# 5__Analog_input_filters.net
KiCad netlist of a schematic drawn in Altium Designer
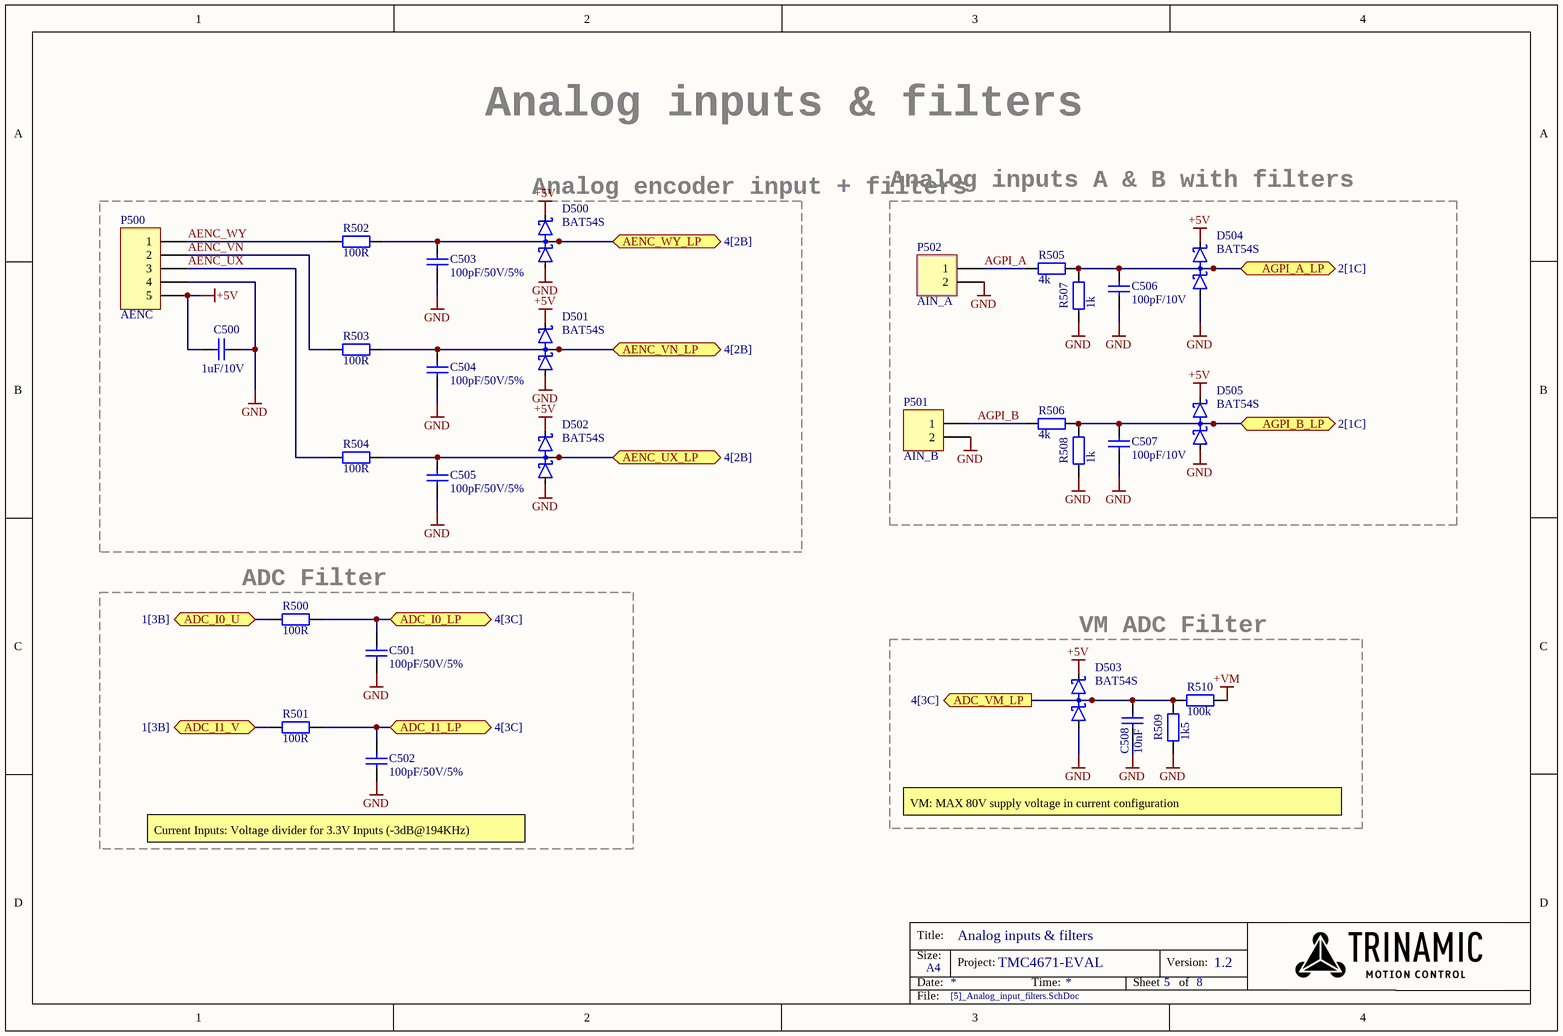
[diagram p0: [5]_Analog_input_filters.SchDoc]

(export (version "E")
  (design (tool "Eeschema 10.0.6"))
  (components
    (comp (ref "C500")
      (value "1uF/10V")
      (footprint "C0603")
      (description "SMD Multilayer Ceramic Capacitor, 0603 [1608 Metric], 1 µF, 10 V, ± 10%, X5R, MC Series")
      (fields (field (name "MF") "MULTICOMP") (field (name "MPN") "MC0603X105K100CT"))
      (libsource (lib "SMD_Passives") (part "C, 1 µF, 10 V, ± 10%, X5R, MC Series, 0603 [1608 Metric]"))
    )
    (comp (ref "C501")
      (value "100pF/50V/5%")
      (footprint "C0603")
      (description "SMD Multilayer Ceramic Capacitor, 0603 [1608 Metric], 100 pF, 50 V, ± 5%, C0G / NP0, MC Series")
      (fields (field (name "MF") "MULTICOMP") (field (name "MPN") "MC0603N101J500CT"))
      (libsource (lib "SMD_Passives") (part "C, 100 pF, 50 V, ± 5%, C0G / NP0, MC Series, 0603 [1608 Metric]"))
    )
    (comp (ref "C502")
      (value "100pF/50V/5%")
      (footprint "C0603")
      (description "SMD Multilayer Ceramic Capacitor, 0603 [1608 Metric], 100 pF, 50 V, ± 5%, C0G / NP0, MC Series")
      (fields (field (name "MF") "MULTICOMP") (field (name "MPN") "MC0603N101J500CT"))
      (libsource (lib "SMD_Passives") (part "C, 100 pF, 50 V, ± 5%, C0G / NP0, MC Series, 0603 [1608 Metric]"))
    )
    (comp (ref "C503")
      (value "100pF/50V/5%")
      (footprint "C0603")
      (description "SMD Multilayer Ceramic Capacitor, 0603 [1608 Metric], 100 pF, 50 V, ± 5%, C0G / NP0, MC Series")
      (fields (field (name "MF") "MULTICOMP") (field (name "MPN") "MC0603N101J500CT"))
      (libsource (lib "SMD_Passives") (part "C, 100 pF, 50 V, ± 5%, C0G / NP0, MC Series, 0603 [1608 Metric]"))
    )
    (comp (ref "C504")
      (value "100pF/50V/5%")
      (footprint "C0603")
      (description "SMD Multilayer Ceramic Capacitor, 0603 [1608 Metric], 100 pF, 50 V, ± 5%, C0G / NP0, MC Series")
      (fields (field (name "MF") "MULTICOMP") (field (name "MPN") "MC0603N101J500CT"))
      (libsource (lib "SMD_Passives") (part "C, 100 pF, 50 V, ± 5%, C0G / NP0, MC Series, 0603 [1608 Metric]"))
    )
    (comp (ref "C505")
      (value "100pF/50V/5%")
      (footprint "C0603")
      (description "SMD Multilayer Ceramic Capacitor, 0603 [1608 Metric], 100 pF, 50 V, ± 5%, C0G / NP0, MC Series")
      (fields (field (name "MF") "MULTICOMP") (field (name "MPN") "MC0603N101J500CT"))
      (libsource (lib "SMD_Passives") (part "C, 100 pF, 50 V, ± 5%, C0G / NP0, MC Series, 0603 [1608 Metric]"))
    )
    (comp (ref "C506")
      (value "100pF/10V")
      (footprint "C0603")
      (description "SMD Multilayer Ceramic Capacitor, 0603 [1608 Metric], 100 pF, 10 V, ± 1%, C0G / NP0, MCMT Series")
      (fields (field (name "MF") "MULTICOMP") (field (name "MPN") "MCMT18N101F100CT"))
      (libsource (lib "SMD_Passives") (part "C, 100 pF, 10 V, ± 1%, C0G / NP0, MCMT Series, 0603 [1608 Metric]"))
    )
    (comp (ref "C507")
      (value "100pF/10V")
      (footprint "C0603")
      (description "SMD Multilayer Ceramic Capacitor, 0603 [1608 Metric], 100 pF, 10 V, ± 1%, C0G / NP0, MCMT Series")
      (fields (field (name "MF") "MULTICOMP") (field (name "MPN") "MCMT18N101F100CT"))
      (libsource (lib "SMD_Passives") (part "C, 100 pF, 10 V, ± 1%, C0G / NP0, MCMT Series, 0603 [1608 Metric]"))
    )
    (comp (ref "C508")
      (value "10nF")
      (footprint "C0603")
      (description "SMD Multilayer Ceramic Capacitor, 0603 [1608 Metric], 0.01 µF, 10 V, ± 10%, X7R, MCSH Series")
      (fields (field (name "MF") "MULTICOMP") (field (name "MPN") "MCSH18B103K100CT"))
      (libsource (lib "SMD_Passives") (part "C, 10nF, 10 V, ± 10%, X7R, 0603"))
    )
    (comp (ref "D500")
      (value "BAT54S")
      (footprint "SOT95P237X130-3N")
      (description "Small Signal Schottky Diode, Dual Series, 30 V, 200 mA, 1 V, 600 mA, 125 °C")
      (fields (field (name "MF") "TAIWAN SEMICONDUCTOR"))
      (libsource (lib "TMC4671-EVAL_V1_0") (part "BAT54S"))
    )
    (comp (ref "D501")
      (value "BAT54S")
      (footprint "SOT95P237X130-3N")
      (description "Small Signal Schottky Diode, Dual Series, 30 V, 200 mA, 1 V, 600 mA, 125 °C")
      (fields (field (name "MF") "TAIWAN SEMICONDUCTOR"))
      (libsource (lib "TMC4671-EVAL_V1_0") (part "BAT54S"))
    )
    (comp (ref "D502")
      (value "BAT54S")
      (footprint "SOT95P237X130-3N")
      (description "Small Signal Schottky Diode, Dual Series, 30 V, 200 mA, 1 V, 600 mA, 125 °C")
      (fields (field (name "MF") "TAIWAN SEMICONDUCTOR"))
      (libsource (lib "TMC4671-EVAL_V1_0") (part "BAT54S"))
    )
    (comp (ref "D503")
      (value "BAT54S")
      (footprint "SOT95P237X130-3N")
      (description "Small Signal Schottky Diode, Dual Series, 30 V, 200 mA, 1 V, 600 mA, 125 °C")
      (fields (field (name "MF") "TAIWAN SEMICONDUCTOR"))
      (libsource (lib "TMC4671-EVAL_V1_0") (part "BAT54S"))
    )
    (comp (ref "D504")
      (value "BAT54S")
      (footprint "SOT95P237X130-3N")
      (description "Small Signal Schottky Diode, Dual Series, 30 V, 200 mA, 1 V, 600 mA, 125 °C")
      (fields (field (name "MF") "TAIWAN SEMICONDUCTOR"))
      (libsource (lib "TMC4671-EVAL_V1_0") (part "BAT54S"))
    )
    (comp (ref "D505")
      (value "BAT54S")
      (footprint "SOT95P237X130-3N")
      (description "Small Signal Schottky Diode, Dual Series, 30 V, 200 mA, 1 V, 600 mA, 125 °C")
      (fields (field (name "MF") "TAIWAN SEMICONDUCTOR"))
      (libsource (lib "TMC4671-EVAL_V1_0") (part "BAT54S"))
    )
    (comp (ref "P500")
      (value "AENC")
      (footprint "TH_HDR_1X5")
      (description "Header, 5-Pin")
      (libsource (lib "Miscellaneous Connectors") (part "Header 5"))
    )
    (comp (ref "P501")
      (value "AIN_B")
      (footprint "TH_HDR_1X2")
      (description "Header, 2-Pin")
      (libsource (lib "Miscellaneous Connectors") (part "Header 2"))
    )
    (comp (ref "P502")
      (value "AIN_A")
      (footprint "TH_HDR_1X2")
      (description "Header, 2-Pin")
      (libsource (lib "Miscellaneous Connectors") (part "Header 2"))
    )
    (comp (ref "R500")
      (value "100R")
      (footprint "R0603")
      (description "SMD Chip Resistor, Thick Film, 100 ohm, 50 V, 0603 [1608 Metric], 100 mW, ± 1%, MCWR Series")
      (fields
        (field (name "MPN") "MCWR06X1000FTL")
        (field (name "MF") "MULTICOMP")
        (field (name "RESISTANCE") "100R")
      )
      (libsource (lib "SMD_Passives") (part "R, 100 ohm, 50 V, 0603 [1608 Metric], 100 mW, ± 1%, MCWR Series"))
    )
    (comp (ref "R501")
      (value "100R")
      (footprint "R0603")
      (description "SMD Chip Resistor, Thick Film, 100 ohm, 50 V, 0603 [1608 Metric], 100 mW, ± 1%, MCWR Series")
      (fields
        (field (name "MPN") "MCWR06X1000FTL")
        (field (name "MF") "MULTICOMP")
        (field (name "RESISTANCE") "100R")
      )
      (libsource (lib "SMD_Passives") (part "R, 100 ohm, 50 V, 0603 [1608 Metric], 100 mW, ± 1%, MCWR Series"))
    )
    (comp (ref "R502")
      (value "100R")
      (footprint "R0603")
      (description "SMD Chip Resistor, Thick Film, 100 ohm, 50 V, 0603 [1608 Metric], 100 mW, ± 1%, MCWR Series")
      (fields
        (field (name "MPN") "MCWR06X1000FTL")
        (field (name "MF") "MULTICOMP")
        (field (name "RESISTANCE") "100R")
      )
      (libsource (lib "SMD_Passives") (part "R, 100 ohm, 50 V, 0603 [1608 Metric], 100 mW, ± 1%, MCWR Series"))
    )
    (comp (ref "R503")
      (value "100R")
      (footprint "R0603")
      (description "SMD Chip Resistor, Thick Film, 100 ohm, 50 V, 0603 [1608 Metric], 100 mW, ± 1%, MCWR Series")
      (fields
        (field (name "MPN") "MCWR06X1000FTL")
        (field (name "MF") "MULTICOMP")
        (field (name "RESISTANCE") "100R")
      )
      (libsource (lib "SMD_Passives") (part "R, 100 ohm, 50 V, 0603 [1608 Metric], 100 mW, ± 1%, MCWR Series"))
    )
    (comp (ref "R504")
      (value "100R")
      (footprint "R0603")
      (description "SMD Chip Resistor, Thick Film, 100 ohm, 50 V, 0603 [1608 Metric], 100 mW, ± 1%, MCWR Series")
      (fields
        (field (name "MPN") "MCWR06X1000FTL")
        (field (name "MF") "MULTICOMP")
        (field (name "RESISTANCE") "100R")
      )
      (libsource (lib "SMD_Passives") (part "R, 100 ohm, 50 V, 0603 [1608 Metric], 100 mW, ± 1%, MCWR Series"))
    )
    (comp (ref "R505")
      (value "4k")
      (footprint "R0805")
      (description "SMD Chip Resistor, Thick Film, 4 kohm, 150 V, 0805 [2012 Metric], 125 mW, ± 1%, CRCW Series")
      (fields
        (field (name "MPN") "CRCW08054K00FKTA")
        (field (name "MF") "VISHAY")
        (field (name "RESISTANCE") "4k")
      )
      (libsource (lib "SMD_Passives") (part "R, 4 kohm, 150 V, 0805 [2012 Metric], 125 mW, ± 1%, CRCW Series"))
    )
    (comp (ref "R506")
      (value "4k")
      (footprint "R0805")
      (description "SMD Chip Resistor, Thick Film, 4 kohm, 150 V, 0805 [2012 Metric], 125 mW, ± 1%, CRCW Series")
      (fields
        (field (name "MPN") "CRCW08054K00FKTA")
        (field (name "MF") "VISHAY")
        (field (name "RESISTANCE") "4k")
      )
      (libsource (lib "SMD_Passives") (part "R, 4 kohm, 150 V, 0805 [2012 Metric], 125 mW, ± 1%, CRCW Series"))
    )
    (comp (ref "R507")
      (value "1k")
      (footprint "R0603")
      (description "SMD Chip Resistor, Thick Film, 1 kohm, 50 V, 0603 [1608 Metric], 100 mW, ± 0.5%, RE Series")
      (fields
        (field (name "MPN") "MC0063W060311K")
        (field (name "MF") "MULTICOMP")
        (field (name "RESISTANCE") "1k")
      )
      (libsource (lib "SMD_Passives") (part "R, 1 kohm, 50 V, 0603 [1608 Metric], 63 mW, ± 1%, MC Series"))
    )
    (comp (ref "R508")
      (value "1k")
      (footprint "R0603")
      (description "SMD Chip Resistor, Thick Film, 1 kohm, 50 V, 0603 [1608 Metric], 100 mW, ± 0.5%, RE Series")
      (fields
        (field (name "MPN") "MC0063W060311K")
        (field (name "MF") "MULTICOMP")
        (field (name "RESISTANCE") "1k")
      )
      (libsource (lib "SMD_Passives") (part "R, 1 kohm, 50 V, 0603 [1608 Metric], 63 mW, ± 1%, MC Series"))
    )
    (comp (ref "R509")
      (value "1k5")
      (footprint "R0603")
      (description "SMD Chip Resistor, Thick Film, 1.5 kohm, 50 V, 0603 [1608 Metric], 100 mW, ± 1%, MCWR Series")
      (fields
        (field (name "MPN") "MCWR06X1501FTL")
        (field (name "MF") "MULTICOMP")
        (field (name "RESISTANCE") "1k5")
      )
      (libsource (lib "SMD_Passives") (part "R, 1.5 kohm, 50 V, 0603 [1608 Metric], 100 mW, ± 1%, MCWR Series"))
    )
    (comp (ref "R510")
      (value "100k")
      (footprint "R0603")
      (description "SMD Chip Resistor, Thick Film, 100 kohm, 50 V, 0603 [1608 Metric], 100 mW, ± 1%, MCWR Series")
      (fields
        (field (name "MPN") "MCWR06X1003FTL")
        (field (name "MF") "MULTICOMP")
        (field (name "RESISTANCE") "100k")
      )
      (libsource (lib "SMD_Passives") (part "R, 100 kohm, 50 V, 0603 [1608 Metric], 100 mW, ± 1%, MCWR Series"))
    )
  )
  (nets
    (net (code "1") (name "+5V") (class "Default")
      (node (ref "C500") (pin "2") (pinfunction "2_2") (pintype "passive"))
      (node (ref "D500") (pin "2") (pinfunction "C2_2") (pintype "passive"))
      (node (ref "D501") (pin "2") (pinfunction "C2_2") (pintype "passive"))
      (node (ref "D502") (pin "2") (pinfunction "C2_2") (pintype "passive"))
      (node (ref "D503") (pin "2") (pinfunction "C2_2") (pintype "passive"))
      (node (ref "D504") (pin "2") (pinfunction "C2_2") (pintype "passive"))
      (node (ref "D505") (pin "2") (pinfunction "C2_2") (pintype "passive"))
      (node (ref "P500") (pin "5") (pinfunction "5_5") (pintype "passive"))
    )
    (net (code "2") (name "+VM") (class "Default")
      (node (ref "R510") (pin "2") (pinfunction "2_2") (pintype "passive"))
    )
    (net (code "3") (name "/ADC_I0_LP") (class "Default")
      (node (ref "C501") (pin "2") (pinfunction "2_2") (pintype "passive"))
      (node (ref "R500") (pin "1") (pinfunction "1_1") (pintype "passive"))
    )
    (net (code "4") (name "/ADC_I0_U") (class "Default")
      (node (ref "R500") (pin "2") (pinfunction "2_2") (pintype "passive"))
    )
    (net (code "5") (name "/ADC_I1_LP") (class "Default")
      (node (ref "C502") (pin "2") (pinfunction "2_2") (pintype "passive"))
      (node (ref "R501") (pin "1") (pinfunction "1_1") (pintype "passive"))
    )
    (net (code "6") (name "/ADC_I1_V") (class "Default")
      (node (ref "R501") (pin "2") (pinfunction "2_2") (pintype "passive"))
    )
    (net (code "7") (name "/ADC_VM_LP") (class "Default")
      (node (ref "C508") (pin "2") (pinfunction "2_2") (pintype "passive"))
      (node (ref "D503") (pin "3") (pinfunction "C1A2_3") (pintype "passive"))
      (node (ref "R509") (pin "1") (pinfunction "1_1") (pintype "passive"))
      (node (ref "R510") (pin "1") (pinfunction "1_1") (pintype "passive"))
    )
    (net (code "8") (name "/AENC_UX") (class "Default")
      (node (ref "P500") (pin "3") (pinfunction "3_3") (pintype "passive"))
      (node (ref "R504") (pin "2") (pinfunction "2_2") (pintype "passive"))
    )
    (net (code "9") (name "/AENC_UX_LP") (class "Default")
      (node (ref "C505") (pin "2") (pinfunction "2_2") (pintype "passive"))
      (node (ref "D502") (pin "3") (pinfunction "C1A2_3") (pintype "passive"))
      (node (ref "R504") (pin "1") (pinfunction "1_1") (pintype "passive"))
    )
    (net (code "10") (name "/AENC_VN") (class "Default")
      (node (ref "P500") (pin "2") (pinfunction "2_2") (pintype "passive"))
      (node (ref "R503") (pin "2") (pinfunction "2_2") (pintype "passive"))
    )
    (net (code "11") (name "/AENC_VN_LP") (class "Default")
      (node (ref "C504") (pin "2") (pinfunction "2_2") (pintype "passive"))
      (node (ref "D501") (pin "3") (pinfunction "C1A2_3") (pintype "passive"))
      (node (ref "R503") (pin "1") (pinfunction "1_1") (pintype "passive"))
    )
    (net (code "12") (name "/AENC_WY") (class "Default")
      (node (ref "P500") (pin "1") (pinfunction "1_1") (pintype "passive"))
      (node (ref "R502") (pin "2") (pinfunction "2_2") (pintype "passive"))
    )
    (net (code "13") (name "/AENC_WY_LP") (class "Default")
      (node (ref "C503") (pin "2") (pinfunction "2_2") (pintype "passive"))
      (node (ref "D500") (pin "3") (pinfunction "C1A2_3") (pintype "passive"))
      (node (ref "R502") (pin "1") (pinfunction "1_1") (pintype "passive"))
    )
    (net (code "14") (name "/AGPI_A") (class "Default")
      (node (ref "P502") (pin "1") (pinfunction "1_1") (pintype "passive"))
      (node (ref "R505") (pin "2") (pinfunction "2_2") (pintype "passive"))
    )
    (net (code "15") (name "/AGPI_A_LP") (class "Default")
      (node (ref "C506") (pin "2") (pinfunction "2_2") (pintype "passive"))
      (node (ref "D504") (pin "3") (pinfunction "C1A2_3") (pintype "passive"))
      (node (ref "R505") (pin "1") (pinfunction "1_1") (pintype "passive"))
      (node (ref "R507") (pin "1") (pinfunction "1_1") (pintype "passive"))
    )
    (net (code "16") (name "/AGPI_B") (class "Default")
      (node (ref "P501") (pin "1") (pinfunction "1_1") (pintype "passive"))
      (node (ref "R506") (pin "2") (pinfunction "2_2") (pintype "passive"))
    )
    (net (code "17") (name "/AGPI_B_LP") (class "Default")
      (node (ref "C507") (pin "2") (pinfunction "2_2") (pintype "passive"))
      (node (ref "D505") (pin "3") (pinfunction "C1A2_3") (pintype "passive"))
      (node (ref "R506") (pin "1") (pinfunction "1_1") (pintype "passive"))
      (node (ref "R508") (pin "1") (pinfunction "1_1") (pintype "passive"))
    )
    (net (code "18") (name "GND") (class "Default")
      (node (ref "C500") (pin "1") (pinfunction "1_1") (pintype "passive"))
      (node (ref "C501") (pin "1") (pinfunction "1_1") (pintype "passive"))
      (node (ref "C502") (pin "1") (pinfunction "1_1") (pintype "passive"))
      (node (ref "C503") (pin "1") (pinfunction "1_1") (pintype "passive"))
      (node (ref "C504") (pin "1") (pinfunction "1_1") (pintype "passive"))
      (node (ref "C505") (pin "1") (pinfunction "1_1") (pintype "passive"))
      (node (ref "C506") (pin "1") (pinfunction "1_1") (pintype "passive"))
      (node (ref "C507") (pin "1") (pinfunction "1_1") (pintype "passive"))
      (node (ref "C508") (pin "1") (pinfunction "1_1") (pintype "passive"))
      (node (ref "D500") (pin "1") (pinfunction "A1_1") (pintype "passive"))
      (node (ref "D501") (pin "1") (pinfunction "A1_1") (pintype "passive"))
      (node (ref "D502") (pin "1") (pinfunction "A1_1") (pintype "passive"))
      (node (ref "D503") (pin "1") (pinfunction "A1_1") (pintype "passive"))
      (node (ref "D504") (pin "1") (pinfunction "A1_1") (pintype "passive"))
      (node (ref "D505") (pin "1") (pinfunction "A1_1") (pintype "passive"))
      (node (ref "P500") (pin "4") (pinfunction "4_4") (pintype "passive"))
      (node (ref "P501") (pin "2") (pinfunction "2_2") (pintype "passive"))
      (node (ref "P502") (pin "2") (pinfunction "2_2") (pintype "passive"))
      (node (ref "R507") (pin "2") (pinfunction "2_2") (pintype "passive"))
      (node (ref "R508") (pin "2") (pinfunction "2_2") (pintype "passive"))
      (node (ref "R509") (pin "2") (pinfunction "2_2") (pintype "passive"))
    )
  )
)
